# Ethernet-HPS.net
KiCad netlist of a schematic drawn in Altium Designer
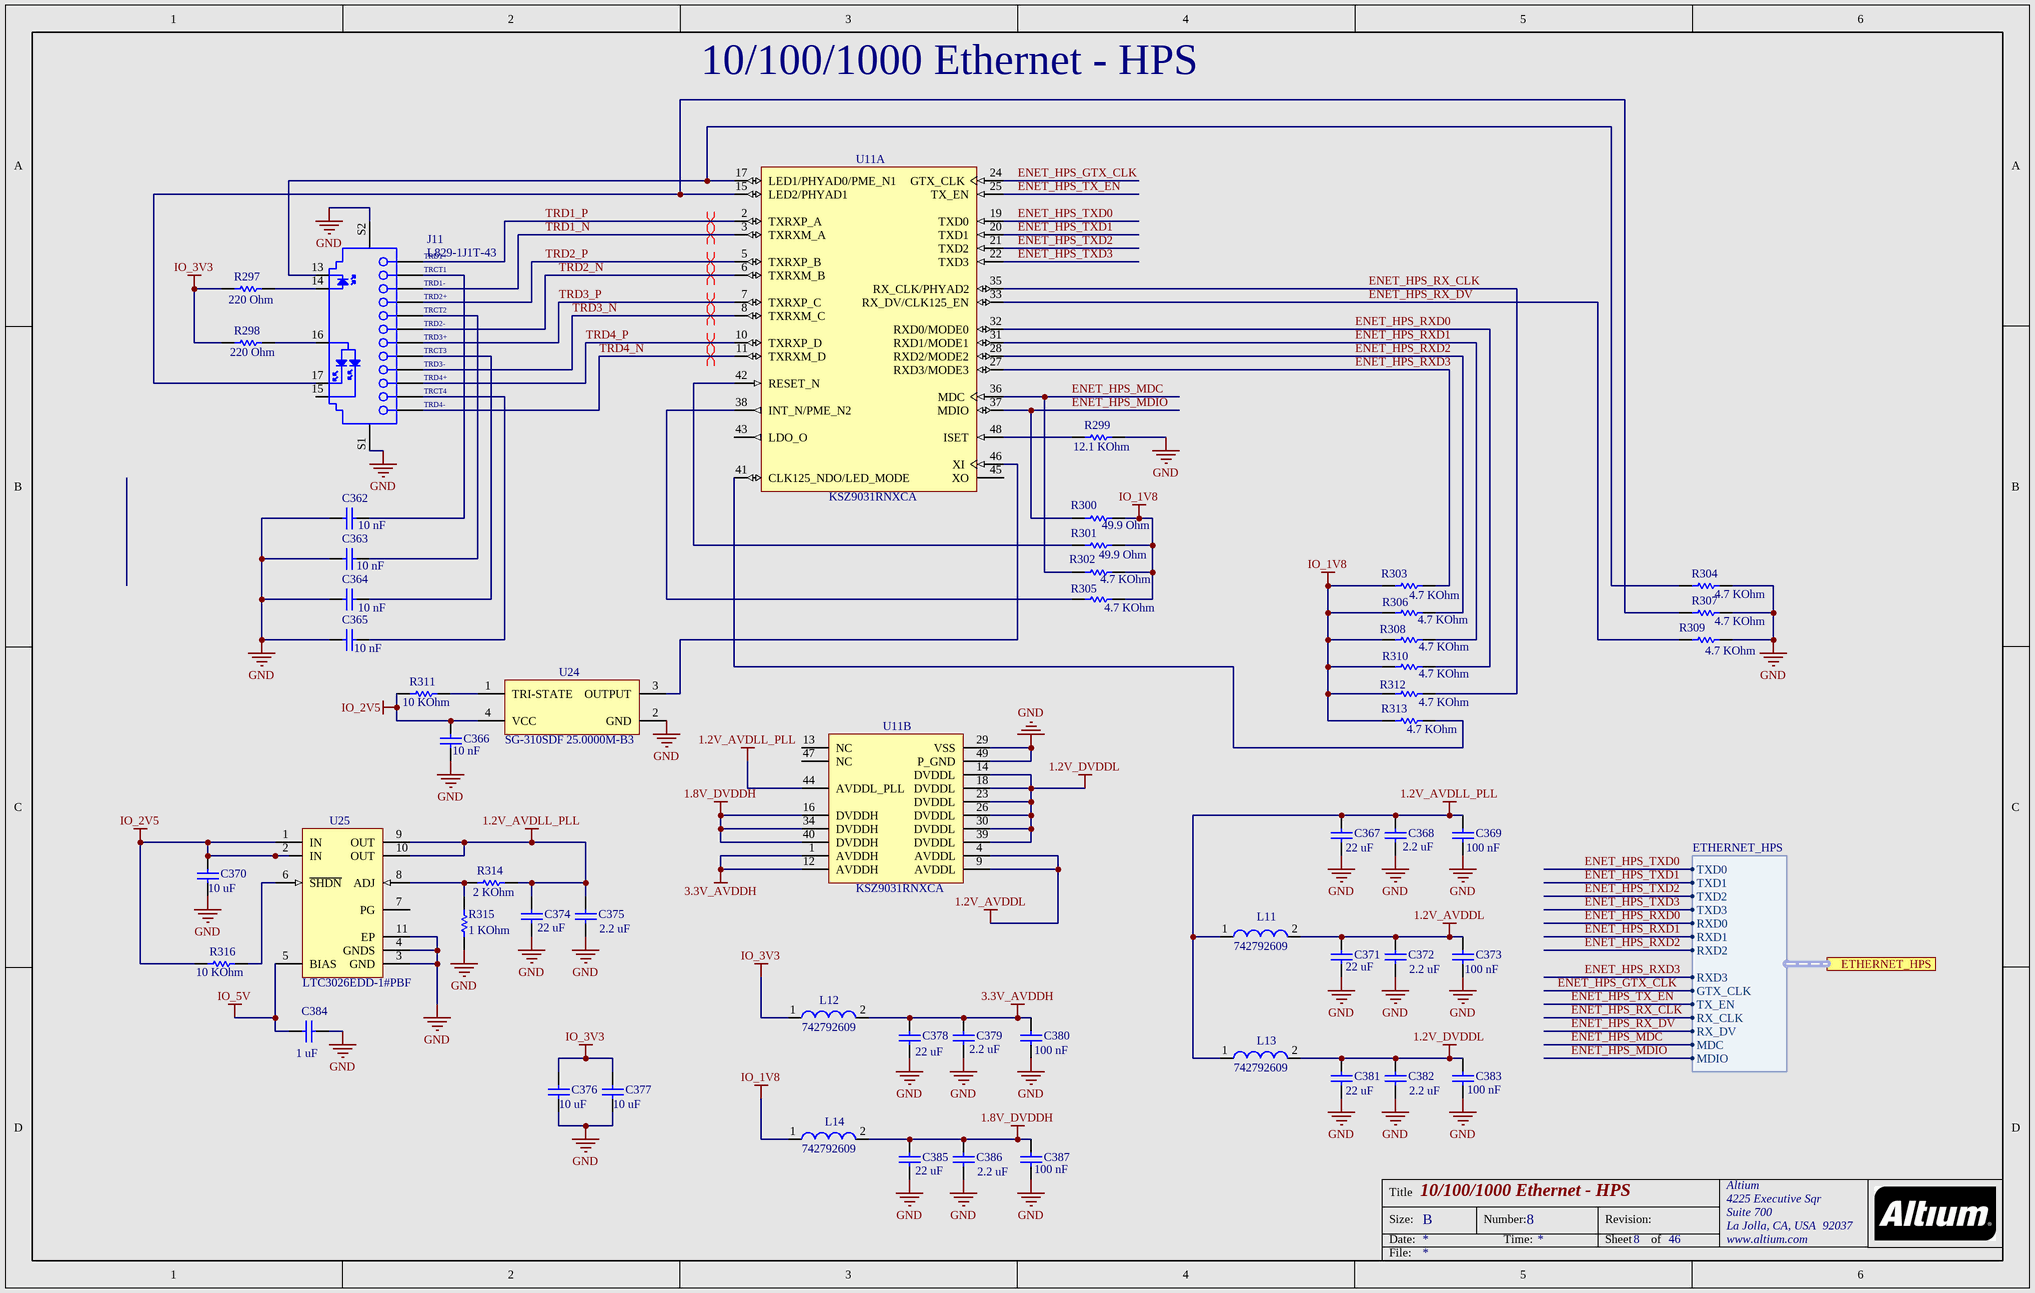
[diagram p0: Ethernet-HPS.SchDoc]

(export (version "E")
  (design (tool "Eeschema 10.0.6"))
  (components
    (comp (ref "C362")
      (value "GRM155R71H103KA88D")
      (footprint "CAPC1005X55X25ML05T10")
      (description "Chip Capacitor, 10 nF, +/- 10%, 50 V, -55 to 125 degC, 0402 (1005 Metric), RoHS, Tape and Reel")
      (fields
        (field (name "TOLERANCE") "10%")
        (field (name "CAPACITANCE") "10 nF")
        (field (name "MANUFACTURER") "Basic Passives")
      )
      (libsource (lib "Altium Content Vault") (part "CAP-NP-2"))
    )
    (comp (ref "C363")
      (value "GRM155R71H103KA88D")
      (footprint "CAPC1005X55X25ML05T10")
      (description "Chip Capacitor, 10 nF, +/- 10%, 50 V, -55 to 125 degC, 0402 (1005 Metric), RoHS, Tape and Reel")
      (fields
        (field (name "TOLERANCE") "10%")
        (field (name "CAPACITANCE") "10 nF")
        (field (name "MANUFACTURER") "Basic Passives")
      )
      (libsource (lib "Altium Content Vault") (part "CAP-NP-2"))
    )
    (comp (ref "C364")
      (value "GRM155R71H103KA88D")
      (footprint "CAPC1005X55X25ML05T10")
      (description "Chip Capacitor, 10 nF, +/- 10%, 50 V, -55 to 125 degC, 0402 (1005 Metric), RoHS, Tape and Reel")
      (fields
        (field (name "TOLERANCE") "10%")
        (field (name "CAPACITANCE") "10 nF")
        (field (name "MANUFACTURER") "Basic Passives")
      )
      (libsource (lib "Altium Content Vault") (part "CAP-NP-2"))
    )
    (comp (ref "C365")
      (value "GRM155R71H103KA88D")
      (footprint "CAPC1005X55X25ML05T10")
      (description "Chip Capacitor, 10 nF, +/- 10%, 50 V, -55 to 125 degC, 0402 (1005 Metric), RoHS, Tape and Reel")
      (fields
        (field (name "TOLERANCE") "10%")
        (field (name "CAPACITANCE") "10 nF")
        (field (name "MANUFACTURER") "Basic Passives")
      )
      (libsource (lib "Altium Content Vault") (part "CAP-NP-2"))
    )
    (comp (ref "C366")
      (value "GRM155R71H103KA88D")
      (footprint "CAPC1005X55X25ML05T10")
      (description "Chip Capacitor, 10 nF, +/- 10%, 50 V, -55 to 125 degC, 0402 (1005 Metric), RoHS, Tape and Reel")
      (fields
        (field (name "TOLERANCE") "10%")
        (field (name "CAPACITANCE") "10 nF")
        (field (name "MANUFACTURER") "Basic Passives")
      )
      (libsource (lib "Altium Content Vault") (part "CAP-NP-2"))
    )
    (comp (ref "C367")
      (value "GRM31CR61E226KE15L")
      (footprint "CAPC3216X180X55ML20T25")
      (description "Chip Capacitor, 22 uF, +/- 10%, 25 V, -55 to 85 degC, 1206 (3216 Metric), RoHS, Tape and Reel")
      (fields (field (name "TOLERANCE") "10%") (field (name "CAPACITANCE") "22 uF"))
      (libsource (lib "Altium Content Vault") (part "CAP-NP-2"))
    )
    (comp (ref "C368")
      (value "GRM188R61A225KE34x")
      (footprint "CAPC1608X90X35ML10T15")
      (description "Chip Capacitor, 2.2 uF, +/- 10%, 10 V, -55 to 85 degC, 0603 (1608 Metric), RoHS, Tape and Reel")
      (fields (field (name "TOLERANCE") "10%") (field (name "CAPACITANCE") "2.2 uF"))
      (libsource (lib "") (part "CAP-NP-2_1"))
    )
    (comp (ref "C369")
      (value "C1005X7R1E104M")
      (footprint "CAPC1005X55X10LL05")
      (description "Chip Capacitor, 0.1 uF, +/- 20%, 25 V, -55 to 125 degC, 0402 (1005 Metric), RoHS, Tape and Reel")
      (fields (field (name "TOLERANCE") "20%") (field (name "CAPACITANCE") "100 nF"))
      (libsource (lib "Altium Content Vault") (part "CAP-NP-2"))
    )
    (comp (ref "C370")
      (value "C2012X5R1C106K085AC")
      (footprint "CAPC2013X100X20NL20")
      (description "Chip Capacitor, 10 uF, +/- 10%, 16 V, -55 to 85 degC, 0805 (2012 Metric), RoHS, Tape and Reel")
      (fields (field (name "TOLERANCE") "10%") (field (name "CAPACITANCE") "10 uF"))
      (libsource (lib "") (part "CAP-NP-2_1"))
    )
    (comp (ref "C371")
      (value "GRM31CR61E226KE15L")
      (footprint "CAPC3216X180X55ML20T25")
      (description "Chip Capacitor, 22 uF, +/- 10%, 25 V, -55 to 85 degC, 1206 (3216 Metric), RoHS, Tape and Reel")
      (fields (field (name "TOLERANCE") "10%") (field (name "CAPACITANCE") "22 uF"))
      (libsource (lib "Altium Content Vault") (part "CAP-NP-2"))
    )
    (comp (ref "C372")
      (value "GRM188R61A225KE34x")
      (footprint "CAPC1608X90X35ML10T15")
      (description "Chip Capacitor, 2.2 uF, +/- 10%, 10 V, -55 to 85 degC, 0603 (1608 Metric), RoHS, Tape and Reel")
      (fields (field (name "TOLERANCE") "10%") (field (name "CAPACITANCE") "2.2 uF"))
      (libsource (lib "") (part "CAP-NP-2_1"))
    )
    (comp (ref "C373")
      (value "C1005X7R1E104M")
      (footprint "CAPC1005X55X10LL05")
      (description "Chip Capacitor, 0.1 uF, +/- 20%, 25 V, -55 to 125 degC, 0402 (1005 Metric), RoHS, Tape and Reel")
      (fields (field (name "TOLERANCE") "20%") (field (name "CAPACITANCE") "100 nF"))
      (libsource (lib "Altium Content Vault") (part "CAP-NP-2"))
    )
    (comp (ref "C374")
      (value "GRM31CR61E226KE15L")
      (footprint "CAPC3216X180X55ML20T25")
      (description "Chip Capacitor, 22 uF, +/- 10%, 25 V, -55 to 85 degC, 1206 (3216 Metric), RoHS, Tape and Reel")
      (fields (field (name "TOLERANCE") "10%") (field (name "CAPACITANCE") "22 uF"))
      (libsource (lib "Altium Content Vault") (part "CAP-NP-2"))
    )
    (comp (ref "C375")
      (value "GRM188R61A225KE34x")
      (footprint "CAPC1608X90X35ML10T15")
      (description "Chip Capacitor, 2.2 uF, +/- 10%, 10 V, -55 to 85 degC, 0603 (1608 Metric), RoHS, Tape and Reel")
      (fields (field (name "TOLERANCE") "10%") (field (name "CAPACITANCE") "2.2 uF"))
      (libsource (lib "") (part "CAP-NP-2_1"))
    )
    (comp (ref "C376")
      (value "C2012X5R1C106K085AC")
      (footprint "CAPC2013X100X20NL20")
      (description "Chip Capacitor, 10 uF, +/- 10%, 16 V, -55 to 85 degC, 0805 (2012 Metric), RoHS, Tape and Reel")
      (fields (field (name "TOLERANCE") "10%") (field (name "CAPACITANCE") "10 uF"))
      (libsource (lib "") (part "CAP-NP-2_1"))
    )
    (comp (ref "C377")
      (value "C2012X5R1C106K085AC")
      (footprint "CAPC2013X100X20NL20")
      (description "Chip Capacitor, 10 uF, +/- 10%, 16 V, -55 to 85 degC, 0805 (2012 Metric), RoHS, Tape and Reel")
      (fields (field (name "TOLERANCE") "10%") (field (name "CAPACITANCE") "10 uF"))
      (libsource (lib "") (part "CAP-NP-2_1"))
    )
    (comp (ref "C378")
      (value "GRM31CR61E226KE15L")
      (footprint "CAPC3216X180X55ML20T25")
      (description "Chip Capacitor, 22 uF, +/- 10%, 25 V, -55 to 85 degC, 1206 (3216 Metric), RoHS, Tape and Reel")
      (fields (field (name "TOLERANCE") "10%") (field (name "CAPACITANCE") "22 uF"))
      (libsource (lib "Altium Content Vault") (part "CAP-NP-2"))
    )
    (comp (ref "C379")
      (value "GRM188R61A225KE34x")
      (footprint "CAPC1608X90X35ML10T15")
      (description "Chip Capacitor, 2.2 uF, +/- 10%, 10 V, -55 to 85 degC, 0603 (1608 Metric), RoHS, Tape and Reel")
      (fields (field (name "TOLERANCE") "10%") (field (name "CAPACITANCE") "2.2 uF"))
      (libsource (lib "") (part "CAP-NP-2_1"))
    )
    (comp (ref "C380")
      (value "C1005X7R1E104M")
      (footprint "CAPC1005X55X10LL05")
      (description "Chip Capacitor, 0.1 uF, +/- 20%, 25 V, -55 to 125 degC, 0402 (1005 Metric), RoHS, Tape and Reel")
      (fields (field (name "TOLERANCE") "20%") (field (name "CAPACITANCE") "100 nF"))
      (libsource (lib "Altium Content Vault") (part "CAP-NP-2"))
    )
    (comp (ref "C381")
      (value "GRM31CR61E226KE15L")
      (footprint "CAPC3216X180X55ML20T25")
      (description "Chip Capacitor, 22 uF, +/- 10%, 25 V, -55 to 85 degC, 1206 (3216 Metric), RoHS, Tape and Reel")
      (fields (field (name "TOLERANCE") "10%") (field (name "CAPACITANCE") "22 uF"))
      (libsource (lib "Altium Content Vault") (part "CAP-NP-2"))
    )
    (comp (ref "C382")
      (value "GRM188R61A225KE34x")
      (footprint "CAPC1608X90X35ML10T15")
      (description "Chip Capacitor, 2.2 uF, +/- 10%, 10 V, -55 to 85 degC, 0603 (1608 Metric), RoHS, Tape and Reel")
      (fields (field (name "TOLERANCE") "10%") (field (name "CAPACITANCE") "2.2 uF"))
      (libsource (lib "") (part "CAP-NP-2_1"))
    )
    (comp (ref "C383")
      (value "C1005X7R1E104M")
      (footprint "CAPC1005X55X10LL05")
      (description "Chip Capacitor, 0.1 uF, +/- 20%, 25 V, -55 to 125 degC, 0402 (1005 Metric), RoHS, Tape and Reel")
      (fields (field (name "TOLERANCE") "20%") (field (name "CAPACITANCE") "100 nF"))
      (libsource (lib "Altium Content Vault") (part "CAP-NP-2"))
    )
    (comp (ref "C384")
      (value "CGB2A1X5R1E105K033BC")
      (footprint "CAPC1005X33X10LL5")
      (description "Chip Capacitor, 1 uF, +/- 10%, 25 V, -55 to 85 degC, 0402 (1005 Metric), RoHS, Tape and Reel")
      (fields (field (name "CAPACITANCE") "1 uF") (field (name "TOLERANCE") "10%"))
      (libsource (lib "") (part "CAP-NP-2_1"))
    )
    (comp (ref "C385")
      (value "GRM31CR61E226KE15L")
      (footprint "CAPC3216X180X55ML20T25")
      (description "Chip Capacitor, 22 uF, +/- 10%, 25 V, -55 to 85 degC, 1206 (3216 Metric), RoHS, Tape and Reel")
      (fields (field (name "TOLERANCE") "10%") (field (name "CAPACITANCE") "22 uF"))
      (libsource (lib "Altium Content Vault") (part "CAP-NP-2"))
    )
    (comp (ref "C386")
      (value "GRM188R61A225KE34x")
      (footprint "CAPC1608X90X35ML10T15")
      (description "Chip Capacitor, 2.2 uF, +/- 10%, 10 V, -55 to 85 degC, 0603 (1608 Metric), RoHS, Tape and Reel")
      (fields (field (name "TOLERANCE") "10%") (field (name "CAPACITANCE") "2.2 uF"))
      (libsource (lib "") (part "CAP-NP-2_1"))
    )
    (comp (ref "C387")
      (value "C1005X7R1E104M")
      (footprint "CAPC1005X55X10LL05")
      (description "Chip Capacitor, 0.1 uF, +/- 20%, 25 V, -55 to 125 degC, 0402 (1005 Metric), RoHS, Tape and Reel")
      (fields (field (name "TOLERANCE") "20%") (field (name "CAPACITANCE") "100 nF"))
      (libsource (lib "Altium Content Vault") (part "CAP-NP-2"))
    )
    (comp (ref "J11")
      (value "L829-1J1T-43")
      (footprint "BELS-L829-1J1T-43_V")
      (description "Gigabit MagJack(R) Ultra Low Profile, 10/100/1000 Base-T, 19-Pin THD, RoHS, Tray")
      (libsource (lib "Altium Content Vault") (part "RJ45-17-2SHLD"))
    )
    (comp (ref "L11")
      (value "742792609")
      (footprint "SMD-0603")
      (description "SMD EMI Suppression Ferrite Bead WE-CBF, Z = 30 Ohm")
      (libsource (lib "Altium Content Vault") (part "CMP-0220-00193-1"))
    )
    (comp (ref "L12")
      (value "742792609")
      (footprint "SMD-0603")
      (description "SMD EMI Suppression Ferrite Bead WE-CBF, Z = 30 Ohm")
      (libsource (lib "Altium Content Vault") (part "CMP-0220-00193-1"))
    )
    (comp (ref "L13")
      (value "742792609")
      (footprint "SMD-0603")
      (description "SMD EMI Suppression Ferrite Bead WE-CBF, Z = 30 Ohm")
      (libsource (lib "Altium Content Vault") (part "CMP-0220-00193-1"))
    )
    (comp (ref "L14")
      (value "742792609")
      (footprint "SMD-0603")
      (description "SMD EMI Suppression Ferrite Bead WE-CBF, Z = 30 Ohm")
      (libsource (lib "Altium Content Vault") (part "CMP-0220-00193-1"))
    )
    (comp (ref "R297")
      (value "ERJ-2GEJ221X")
      (footprint "RESC1005X40X25LL05T05")
      (description "Chip Resistor, 220 Ohm, +/- 5%, 100 mW, -55 to 155 degC, 0402 (1005 Metric), RoHS, Tape and Reel")
      (fields
        (field (name "RESISTANCE") "220 Ohm")
        (field (name "TOLERANCE") "5%")
        (field (name "MANUFACTURER") "Basic Passives")
      )
      (libsource (lib "Altium Content Vault") (part "RES-2"))
    )
    (comp (ref "R298")
      (value "ERJ-2GEJ221X")
      (footprint "RESC1005X40X25LL05T05")
      (description "Chip Resistor, 220 Ohm, +/- 5%, 100 mW, -55 to 155 degC, 0402 (1005 Metric), RoHS, Tape and Reel")
      (fields
        (field (name "RESISTANCE") "220 Ohm")
        (field (name "TOLERANCE") "5%")
        (field (name "MANUFACTURER") "Basic Passives")
      )
      (libsource (lib "Altium Content Vault") (part "RES-2"))
    )
    (comp (ref "R299")
      (value "CRCW040212K1FKED")
      (footprint "RESC1005X40X25LL05T05")
      (description "Chip Resistor, 12.1 KOhm, +/- 1%, 63 mW, -55 to 155 degC, 0402 (1005 Metric), RoHS, Tape and Reel")
      (fields
        (field (name "RESISTANCE") "12.1 KOhm")
        (field (name "TOLERANCE") "1%")
        (field (name "MANUFACTURER") "Basic Passives")
      )
      (libsource (lib "Altium Content Vault") (part "RES-2"))
    )
    (comp (ref "R300")
      (value "NRC04F49R9TRF")
      (footprint "RESC1005X35X25NL8T10")
      (description "Chip Resistor, 49.9 Ohm, +/- 1%, 0.06 W, -55 to 155 degC, 0402 (1005 Metric), RoHS, Tape and Reel")
      (fields (field (name "TOLERANCE") "1%") (field (name "RESISTANCE") "49.9 Ohm"))
      (libsource (lib "Altium Content Vault") (part "RES-2"))
    )
    (comp (ref "R301")
      (value "NRC04F49R9TRF")
      (footprint "RESC1005X35X25NL8T10")
      (description "Chip Resistor, 49.9 Ohm, +/- 1%, 0.06 W, -55 to 155 degC, 0402 (1005 Metric), RoHS, Tape and Reel")
      (fields (field (name "TOLERANCE") "1%") (field (name "RESISTANCE") "49.9 Ohm"))
      (libsource (lib "Altium Content Vault") (part "RES-2"))
    )
    (comp (ref "R302")
      (value "ERJ-2RKF4701X")
      (footprint "RESC1005X40X25LL05T05")
      (description "Chip Resistor, 4.7 KOhm, +/- 1%, 0.1 W, -55 to 155 degC, 0402 (1005 Metric), RoHS, Tape and Reel")
      (fields (field (name "TOLERANCE") "1%") (field (name "RESISTANCE") "4.7 KOhm"))
      (libsource (lib "Altium Content Vault") (part "RES-2"))
    )
    (comp (ref "R303")
      (value "ERJ-2RKF4701X")
      (footprint "RESC1005X40X25LL05T05")
      (description "Chip Resistor, 4.7 KOhm, +/- 1%, 0.1 W, -55 to 155 degC, 0402 (1005 Metric), RoHS, Tape and Reel")
      (fields (field (name "TOLERANCE") "1%") (field (name "RESISTANCE") "4.7 KOhm"))
      (libsource (lib "Altium Content Vault") (part "RES-2"))
    )
    (comp (ref "R304")
      (value "ERJ-2RKF4701X")
      (footprint "RESC1005X40X25LL05T05")
      (description "Chip Resistor, 4.7 KOhm, +/- 1%, 0.1 W, -55 to 155 degC, 0402 (1005 Metric), RoHS, Tape and Reel")
      (fields (field (name "TOLERANCE") "1%") (field (name "RESISTANCE") "4.7 KOhm"))
      (libsource (lib "Altium Content Vault") (part "RES-2"))
    )
    (comp (ref "R305")
      (value "ERJ-2RKF4701X")
      (footprint "RESC1005X40X25LL05T05")
      (description "Chip Resistor, 4.7 KOhm, +/- 1%, 0.1 W, -55 to 155 degC, 0402 (1005 Metric), RoHS, Tape and Reel")
      (fields (field (name "TOLERANCE") "1%") (field (name "RESISTANCE") "4.7 KOhm"))
      (libsource (lib "Altium Content Vault") (part "RES-2"))
    )
    (comp (ref "R306")
      (value "ERJ-2RKF4701X")
      (footprint "RESC1005X40X25LL05T05")
      (description "Chip Resistor, 4.7 KOhm, +/- 1%, 0.1 W, -55 to 155 degC, 0402 (1005 Metric), RoHS, Tape and Reel")
      (fields (field (name "TOLERANCE") "1%") (field (name "RESISTANCE") "4.7 KOhm"))
      (libsource (lib "Altium Content Vault") (part "RES-2"))
    )
    (comp (ref "R307")
      (value "ERJ-2RKF4701X")
      (footprint "RESC1005X40X25LL05T05")
      (description "Chip Resistor, 4.7 KOhm, +/- 1%, 0.1 W, -55 to 155 degC, 0402 (1005 Metric), RoHS, Tape and Reel")
      (fields (field (name "TOLERANCE") "1%") (field (name "RESISTANCE") "4.7 KOhm"))
      (libsource (lib "Altium Content Vault") (part "RES-2"))
    )
    (comp (ref "R308")
      (value "ERJ-2RKF4701X")
      (footprint "RESC1005X40X25LL05T05")
      (description "Chip Resistor, 4.7 KOhm, +/- 1%, 0.1 W, -55 to 155 degC, 0402 (1005 Metric), RoHS, Tape and Reel")
      (fields (field (name "TOLERANCE") "1%") (field (name "RESISTANCE") "4.7 KOhm"))
      (libsource (lib "Altium Content Vault") (part "RES-2"))
    )
    (comp (ref "R309")
      (value "ERJ-2RKF4701X")
      (footprint "RESC1005X40X25LL05T05")
      (description "Chip Resistor, 4.7 KOhm, +/- 1%, 0.1 W, -55 to 155 degC, 0402 (1005 Metric), RoHS, Tape and Reel")
      (fields (field (name "TOLERANCE") "1%") (field (name "RESISTANCE") "4.7 KOhm"))
      (libsource (lib "Altium Content Vault") (part "RES-2"))
    )
    (comp (ref "R310")
      (value "ERJ-2RKF4701X")
      (footprint "RESC1005X40X25LL05T05")
      (description "Chip Resistor, 4.7 KOhm, +/- 1%, 0.1 W, -55 to 155 degC, 0402 (1005 Metric), RoHS, Tape and Reel")
      (fields (field (name "TOLERANCE") "1%") (field (name "RESISTANCE") "4.7 KOhm"))
      (libsource (lib "Altium Content Vault") (part "RES-2"))
    )
    (comp (ref "R311")
      (value "ERJ-2RKF1002X")
      (footprint "RESC1005X40X25NL05T05")
      (description "Chip Resistor, 10 KOhm, +/- 1%, 100 mW, -55 to 155 degC, 0402 (1005 Metric), RoHS, Tape and Reel")
      (fields
        (field (name "TOLERANCE") "1%")
        (field (name "RESISTANCE") "10 KOhm")
        (field (name "MANUFACTURER") "Basic Passives")
      )
      (libsource (lib "Altium Content Vault") (part "RES-2"))
    )
    (comp (ref "R312")
      (value "ERJ-2RKF4701X")
      (footprint "RESC1005X40X25LL05T05")
      (description "Chip Resistor, 4.7 KOhm, +/- 1%, 0.1 W, -55 to 155 degC, 0402 (1005 Metric), RoHS, Tape and Reel")
      (fields (field (name "TOLERANCE") "1%") (field (name "RESISTANCE") "4.7 KOhm"))
      (libsource (lib "Altium Content Vault") (part "RES-2"))
    )
    (comp (ref "R313")
      (value "ERJ-2RKF4701X")
      (footprint "RESC1005X40X25LL05T05")
      (description "Chip Resistor, 4.7 KOhm, +/- 1%, 0.1 W, -55 to 155 degC, 0402 (1005 Metric), RoHS, Tape and Reel")
      (fields (field (name "TOLERANCE") "1%") (field (name "RESISTANCE") "4.7 KOhm"))
      (libsource (lib "Altium Content Vault") (part "RES-2"))
    )
    (comp (ref "R314")
      (value "ERJ-2RKF2001X")
      (footprint "RESC1005X40X25NL05T05")
      (description "Chip Resistor, 2 KOhm, +/- 1%, 100 mW, -55 to 155 degC, 0402 (1005 Metric), RoHS, Tape and Reel")
      (fields
        (field (name "TOLERANCE") "1%")
        (field (name "RESISTANCE") "2 KOhm")
        (field (name "MANUFACTURER") "Basic Passives")
      )
      (libsource (lib "Altium Content Vault") (part "RES-2"))
    )
    (comp (ref "R315")
      (value "ERJ-2RKF1001X")
      (footprint "RESC1005X40X25LL05T05")
      (description "Chip Resistor, 1 KOhm, +/- 1%, 100 mW, -55 to 155 degC, 0402 (1005 Metric), RoHS, Tape and Reel")
      (fields
        (field (name "RESISTANCE") "1 KOhm")
        (field (name "TOLERANCE") "1%")
        (field (name "MANUFACTURER") "Basic Passives")
      )
      (libsource (lib "Altium Content Vault") (part "RES-2"))
    )
    (comp (ref "R316")
      (value "ERJ-2RKF1002X")
      (footprint "RESC1005X40X25NL05T05")
      (description "Chip Resistor, 10 KOhm, +/- 1%, 100 mW, -55 to 155 degC, 0402 (1005 Metric), RoHS, Tape and Reel")
      (fields
        (field (name "TOLERANCE") "1%")
        (field (name "RESISTANCE") "10 KOhm")
        (field (name "MANUFACTURER") "Basic Passives")
      )
      (libsource (lib "Altium Content Vault") (part "RES-2"))
    )
    (comp (ref "U11")
      (value "KSZ9031RNXCA")
      (footprint "MICL-QFN-48_V")
      (description "Gigabit Ethernet Transceiver with RGMII Support, 1.14 to 1.26 V, 0 to 70 degC, 48-Pin QFN, RoHS")
      (fields (field (name "MANUFACTURER") "Micrel"))
      (libsource (lib "Altium Content Vault") (part "MICL-KSZ9031RNX-48"))
    )
    (comp (ref "U24")
      (value "SG-310SDF 25.0000M-B3")
      (footprint "EPSON-SG-310-4_V")
      (description "Crystal Oscillator (SPXO), 2.5 V, 25 MHz, -20 to 70 degC, 4-Pin SMD, RoHS, Tape and Reel")
      (libsource (lib "Altium Content Vault") (part "XTAL-1-3-4_B"))
    )
    (comp (ref "U25")
      (value "LTC3026EDD-1#PBF")
      (footprint "LT-DD-10_V")
      (fields (field (name "MANUFACTURER") "Linear Technology"))
      (libsource (lib "Altium Content Vault") (part "LT-LTC3026-1-10"))
    )
  )
  (nets
    (net (code "2") (name "/ENET_HPS_GTX_CLK") (class "Default")
      (node (ref "U11") (pin "24") (pinfunction "GTX_CLK_24") (pintype "input"))
    )
    (net (code "3") (name "/ENET_HPS_MDC") (class "Default")
      (node (ref "R302") (pin "1") (pinfunction "1_1") (pintype "passive"))
      (node (ref "U11") (pin "36") (pinfunction "MDC_36") (pintype "input"))
    )
    (net (code "4") (name "/ENET_HPS_MDIO") (class "Default")
      (node (ref "R300") (pin "1") (pinfunction "1_1") (pintype "passive"))
      (node (ref "U11") (pin "37") (pinfunction "MDIO_37") (pintype "bidirectional"))
    )
    (net (code "5") (name "/ENET_HPS_RXD0") (class "Default")
      (node (ref "R310") (pin "2") (pinfunction "2_2") (pintype "passive"))
      (node (ref "U11") (pin "32") (pinfunction "RXD0/MODE0_32") (pintype "bidirectional"))
    )
    (net (code "6") (name "/ENET_HPS_RXD1") (class "Default")
      (node (ref "R308") (pin "2") (pinfunction "2_2") (pintype "passive"))
      (node (ref "U11") (pin "31") (pinfunction "RXD1/MODE1_31") (pintype "bidirectional"))
    )
    (net (code "7") (name "/ENET_HPS_RXD2") (class "Default")
      (node (ref "R306") (pin "2") (pinfunction "2_2") (pintype "passive"))
      (node (ref "U11") (pin "28") (pinfunction "RXD2/MODE2_28") (pintype "bidirectional"))
    )
    (net (code "8") (name "/ENET_HPS_RXD3") (class "Default")
      (node (ref "R303") (pin "2") (pinfunction "2_2") (pintype "passive"))
      (node (ref "U11") (pin "27") (pinfunction "RXD3/MODE3_27") (pintype "bidirectional"))
    )
    (net (code "9") (name "/ENET_HPS_RX_CLK") (class "Default")
      (node (ref "R312") (pin "2") (pinfunction "2_2") (pintype "passive"))
      (node (ref "U11") (pin "35") (pinfunction "RX_CLK/PHYAD2_35") (pintype "bidirectional"))
    )
    (net (code "10") (name "/ENET_HPS_RX_DV") (class "Default")
      (node (ref "R309") (pin "1") (pinfunction "1_1") (pintype "passive"))
      (node (ref "U11") (pin "33") (pinfunction "RX_DV/CLK125_EN_33") (pintype "bidirectional"))
    )
    (net (code "11") (name "/ENET_HPS_TXD0") (class "Default")
      (node (ref "U11") (pin "19") (pinfunction "TXD0_19") (pintype "input"))
    )
    (net (code "12") (name "/ENET_HPS_TXD1") (class "Default")
      (node (ref "U11") (pin "20") (pinfunction "TXD1_20") (pintype "input"))
    )
    (net (code "13") (name "/ENET_HPS_TXD2") (class "Default")
      (node (ref "U11") (pin "21") (pinfunction "TXD2_21") (pintype "input"))
    )
    (net (code "14") (name "/ENET_HPS_TXD3") (class "Default")
      (node (ref "U11") (pin "22") (pinfunction "TXD3_22") (pintype "input"))
    )
    (net (code "15") (name "/ENET_HPS_TX_EN") (class "Default")
      (node (ref "U11") (pin "25") (pinfunction "TX_EN_25") (pintype "input"))
    )
    (net (code "16") (name "/TRD1_N") (class "Default")
      (node (ref "J11") (pin "3") (pinfunction "TRD1-_3") (pintype "passive"))
      (node (ref "U11") (pin "3") (pinfunction "TXRXM_A_3") (pintype "bidirectional"))
    )
    (net (code "17") (name "/TRD1_P") (class "Default")
      (node (ref "J11") (pin "1") (pinfunction "TRD1+_1") (pintype "passive"))
      (node (ref "U11") (pin "2") (pinfunction "TXRXP_A_2") (pintype "bidirectional"))
    )
    (net (code "18") (name "/TRD2_N") (class "Default")
      (node (ref "J11") (pin "6") (pinfunction "TRD2-_6") (pintype "passive"))
      (node (ref "U11") (pin "6") (pinfunction "TXRXM_B_6") (pintype "bidirectional"))
    )
    (net (code "19") (name "/TRD2_P") (class "Default")
      (node (ref "J11") (pin "4") (pinfunction "TRD2+_4") (pintype "passive"))
      (node (ref "U11") (pin "5") (pinfunction "TXRXP_B_5") (pintype "bidirectional"))
    )
    (net (code "20") (name "/TRD3_N") (class "Default")
      (node (ref "J11") (pin "9") (pinfunction "TRD3-_9") (pintype "passive"))
      (node (ref "U11") (pin "8") (pinfunction "TXRXM_C_8") (pintype "bidirectional"))
    )
    (net (code "21") (name "/TRD3_P") (class "Default")
      (node (ref "J11") (pin "7") (pinfunction "TRD3+_7") (pintype "passive"))
      (node (ref "U11") (pin "7") (pinfunction "TXRXP_C_7") (pintype "bidirectional"))
    )
    (net (code "22") (name "/TRD4_N") (class "Default")
      (node (ref "J11") (pin "12") (pinfunction "TRD4-_12") (pintype "passive"))
      (node (ref "U11") (pin "11") (pinfunction "TXRXM_D_11") (pintype "bidirectional"))
    )
    (net (code "23") (name "/TRD4_P") (class "Default")
      (node (ref "J11") (pin "10") (pinfunction "TRD4+_10") (pintype "passive"))
      (node (ref "U11") (pin "10") (pinfunction "TXRXP_D_10") (pintype "bidirectional"))
    )
    (net (code "25") (name "1.2V_AVDDL") (class "Default")
      (node (ref "C371") (pin "2") (pinfunction "2_2") (pintype "passive"))
      (node (ref "C372") (pin "2") (pinfunction "2_2") (pintype "passive"))
      (node (ref "C373") (pin "2") (pinfunction "2_2") (pintype "passive"))
      (node (ref "L11") (pin "2") (pinfunction "2_2") (pintype "passive"))
      (node (ref "U11") (pin "4") (pinfunction "AVDDL_4") (pintype "power_in"))
      (node (ref "U11") (pin "9") (pinfunction "AVDDL_9") (pintype "power_in"))
    )
    (net (code "26") (name "1.2V_AVDLL_PLL") (class "Default")
      (node (ref "C367") (pin "2") (pinfunction "2_2") (pintype "passive"))
      (node (ref "C368") (pin "2") (pinfunction "2_2") (pintype "passive"))
      (node (ref "C369") (pin "2") (pinfunction "2_2") (pintype "passive"))
      (node (ref "C374") (pin "2") (pinfunction "2_2") (pintype "passive"))
      (node (ref "C375") (pin "2") (pinfunction "2_2") (pintype "passive"))
      (node (ref "L11") (pin "1") (pinfunction "1_1") (pintype "passive"))
      (node (ref "L13") (pin "1") (pinfunction "1_1") (pintype "passive"))
      (node (ref "R314") (pin "2") (pinfunction "2_2") (pintype "passive"))
      (node (ref "U11") (pin "44") (pinfunction "AVDDL_PLL_44") (pintype "power_in"))
      (node (ref "U25") (pin "10") (pinfunction "OUT_10") (pintype "power_in"))
      (node (ref "U25") (pin "9") (pinfunction "OUT_9") (pintype "power_in"))
    )
    (net (code "27") (name "1.2V_DVDDL") (class "Default")
      (node (ref "C381") (pin "2") (pinfunction "2_2") (pintype "passive"))
      (node (ref "C382") (pin "2") (pinfunction "2_2") (pintype "passive"))
      (node (ref "C383") (pin "2") (pinfunction "2_2") (pintype "passive"))
      (node (ref "L13") (pin "2") (pinfunction "2_2") (pintype "passive"))
      (node (ref "U11") (pin "14") (pinfunction "DVDDL_14") (pintype "power_in"))
      (node (ref "U11") (pin "18") (pinfunction "DVDDL_18") (pintype "power_in"))
      (node (ref "U11") (pin "23") (pinfunction "DVDDL_23") (pintype "power_in"))
      (node (ref "U11") (pin "26") (pinfunction "DVDDL_26") (pintype "power_in"))
      (node (ref "U11") (pin "30") (pinfunction "DVDDL_30") (pintype "power_in"))
      (node (ref "U11") (pin "39") (pinfunction "DVDDL_39") (pintype "power_in"))
    )
    (net (code "28") (name "1.8V_DVDDH") (class "Default")
      (node (ref "C385") (pin "2") (pinfunction "2_2") (pintype "passive"))
      (node (ref "C386") (pin "2") (pinfunction "2_2") (pintype "passive"))
      (node (ref "C387") (pin "1") (pinfunction "1_1") (pintype "passive"))
      (node (ref "L14") (pin "2") (pinfunction "2_2") (pintype "passive"))
      (node (ref "U11") (pin "16") (pinfunction "DVDDH_16") (pintype "power_in"))
      (node (ref "U11") (pin "34") (pinfunction "DVDDH_34") (pintype "power_in"))
      (node (ref "U11") (pin "40") (pinfunction "DVDDH_40") (pintype "power_in"))
    )
    (net (code "29") (name "3.3V_AVDDH") (class "Default")
      (node (ref "C378") (pin "2") (pinfunction "2_2") (pintype "passive"))
      (node (ref "C379") (pin "2") (pinfunction "2_2") (pintype "passive"))
      (node (ref "C380") (pin "2") (pinfunction "2_2") (pintype "passive"))
      (node (ref "L12") (pin "2") (pinfunction "2_2") (pintype "passive"))
      (node (ref "U11") (pin "1") (pinfunction "AVDDH_1") (pintype "power_in"))
      (node (ref "U11") (pin "12") (pinfunction "AVDDH_12") (pintype "power_in"))
    )
    (net (code "30") (name "GND") (class "Default")
      (node (ref "C362") (pin "1") (pinfunction "1_1") (pintype "passive"))
      (node (ref "C363") (pin "1") (pinfunction "1_1") (pintype "passive"))
      (node (ref "C364") (pin "1") (pinfunction "1_1") (pintype "passive"))
      (node (ref "C365") (pin "1") (pinfunction "1_1") (pintype "passive"))
      (node (ref "C366") (pin "1") (pinfunction "1_1") (pintype "passive"))
      (node (ref "C367") (pin "1") (pinfunction "1_1") (pintype "passive"))
      (node (ref "C368") (pin "1") (pinfunction "1_1") (pintype "passive"))
      (node (ref "C369") (pin "1") (pinfunction "1_1") (pintype "passive"))
      (node (ref "C370") (pin "1") (pinfunction "1_1") (pintype "passive"))
      (node (ref "C371") (pin "1") (pinfunction "1_1") (pintype "passive"))
      (node (ref "C372") (pin "1") (pinfunction "1_1") (pintype "passive"))
      (node (ref "C373") (pin "1") (pinfunction "1_1") (pintype "passive"))
      (node (ref "C374") (pin "1") (pinfunction "1_1") (pintype "passive"))
      (node (ref "C375") (pin "1") (pinfunction "1_1") (pintype "passive"))
      (node (ref "C376") (pin "1") (pinfunction "1_1") (pintype "passive"))
      (node (ref "C377") (pin "1") (pinfunction "1_1") (pintype "passive"))
      (node (ref "C378") (pin "1") (pinfunction "1_1") (pintype "passive"))
      (node (ref "C379") (pin "1") (pinfunction "1_1") (pintype "passive"))
      (node (ref "C380") (pin "1") (pinfunction "1_1") (pintype "passive"))
      (node (ref "C381") (pin "1") (pinfunction "1_1") (pintype "passive"))
      (node (ref "C382") (pin "1") (pinfunction "1_1") (pintype "passive"))
      (node (ref "C383") (pin "1") (pinfunction "1_1") (pintype "passive"))
      (node (ref "C384") (pin "1") (pinfunction "1_1") (pintype "passive"))
      (node (ref "C385") (pin "1") (pinfunction "1_1") (pintype "passive"))
      (node (ref "C386") (pin "1") (pinfunction "1_1") (pintype "passive"))
      (node (ref "C387") (pin "2") (pinfunction "2_2") (pintype "passive"))
      (node (ref "J11") (pin "S1") (pinfunction "S1_S1") (pintype "passive"))
      (node (ref "J11") (pin "S2") (pinfunction "S2_S2") (pintype "passive"))
      (node (ref "R299") (pin "2") (pinfunction "2_2") (pintype "passive"))
      (node (ref "R304") (pin "2") (pinfunction "2_2") (pintype "passive"))
      (node (ref "R307") (pin "2") (pinfunction "2_2") (pintype "passive"))
      (node (ref "R309") (pin "2") (pinfunction "2_2") (pintype "passive"))
      (node (ref "R315") (pin "1") (pinfunction "1_1") (pintype "passive"))
      (node (ref "U11") (pin "29") (pinfunction "VSS_29") (pintype "power_in"))
      (node (ref "U11") (pin "49") (pinfunction "P_GND_49") (pintype "power_in"))
      (node (ref "U24") (pin "2") (pinfunction "GND_2") (pintype "power_in"))
      (node (ref "U25") (pin "11") (pinfunction "EP_11") (pintype "power_in"))
      (node (ref "U25") (pin "3") (pinfunction "GND_3") (pintype "power_in"))
      (node (ref "U25") (pin "4") (pinfunction "GNDS_4") (pintype "power_in"))
    )
    (net (code "31") (name "IO_1V8") (class "Default")
      (node (ref "L14") (pin "1") (pinfunction "1_1") (pintype "passive"))
      (node (ref "R300") (pin "2") (pinfunction "2_2") (pintype "passive"))
      (node (ref "R301") (pin "2") (pinfunction "2_2") (pintype "passive"))
      (node (ref "R302") (pin "2") (pinfunction "2_2") (pintype "passive"))
      (node (ref "R303") (pin "1") (pinfunction "1_1") (pintype "passive"))
      (node (ref "R305") (pin "2") (pinfunction "2_2") (pintype "passive"))
      (node (ref "R306") (pin "1") (pinfunction "1_1") (pintype "passive"))
      (node (ref "R308") (pin "1") (pinfunction "1_1") (pintype "passive"))
      (node (ref "R310") (pin "1") (pinfunction "1_1") (pintype "passive"))
      (node (ref "R312") (pin "1") (pinfunction "1_1") (pintype "passive"))
      (node (ref "R313") (pin "1") (pinfunction "1_1") (pintype "passive"))
    )
    (net (code "32") (name "IO_2V5") (class "Default")
      (node (ref "C366") (pin "2") (pinfunction "2_2") (pintype "passive"))
      (node (ref "C370") (pin "2") (pinfunction "2_2") (pintype "passive"))
      (node (ref "R311") (pin "1") (pinfunction "1_1") (pintype "passive"))
      (node (ref "R316") (pin "1") (pinfunction "1_1") (pintype "passive"))
      (node (ref "U24") (pin "4") (pinfunction "VCC_4") (pintype "power_in"))
      (node (ref "U25") (pin "1") (pinfunction "IN_1") (pintype "power_in"))
      (node (ref "U25") (pin "2") (pinfunction "IN_2") (pintype "power_in"))
    )
    (net (code "33") (name "IO_3V3") (class "Default")
      (node (ref "C376") (pin "2") (pinfunction "2_2") (pintype "passive"))
      (node (ref "C377") (pin "2") (pinfunction "2_2") (pintype "passive"))
      (node (ref "L12") (pin "1") (pinfunction "1_1") (pintype "passive"))
      (node (ref "R297") (pin "1") (pinfunction "1_1") (pintype "passive"))
      (node (ref "R298") (pin "1") (pinfunction "1_1") (pintype "passive"))
    )
    (net (code "34") (name "IO_5V") (class "Default")
      (node (ref "C384") (pin "2") (pinfunction "2_2") (pintype "passive"))
      (node (ref "U25") (pin "5") (pinfunction "BIAS_5") (pintype "power_in"))
    )
    (net (code "35") (name "Net-(J11-Pad14)") (class "Default")
      (node (ref "J11") (pin "14") (pinfunction "14_14") (pintype "passive"))
      (node (ref "R297") (pin "2") (pinfunction "2_2") (pintype "passive"))
    )
    (net (code "36") (name "Net-(J11-Pad16)") (class "Default")
      (node (ref "J11") (pin "16") (pinfunction "16_16") (pintype "passive"))
      (node (ref "R298") (pin "2") (pinfunction "2_2") (pintype "passive"))
    )
    (net (code "37") (name "Net-(J11-TRCT1)") (class "Default")
      (node (ref "C362") (pin "2") (pinfunction "2_2") (pintype "passive"))
      (node (ref "J11") (pin "2") (pinfunction "TRCT1_2") (pintype "passive"))
    )
    (net (code "38") (name "Net-(J11-TRCT2)") (class "Default")
      (node (ref "C363") (pin "2") (pinfunction "2_2") (pintype "passive"))
      (node (ref "J11") (pin "5") (pinfunction "TRCT2_5") (pintype "passive"))
    )
    (net (code "39") (name "Net-(J11-TRCT3)") (class "Default")
      (node (ref "C364") (pin "2") (pinfunction "2_2") (pintype "passive"))
      (node (ref "J11") (pin "8") (pinfunction "TRCT3_8") (pintype "passive"))
    )
    (net (code "40") (name "Net-(J11-TRCT4)") (class "Default")
      (node (ref "C365") (pin "2") (pinfunction "2_2") (pintype "passive"))
      (node (ref "J11") (pin "11") (pinfunction "TRCT4_11") (pintype "passive"))
    )
    (net (code "41") (name "Net-(U11A-CLK125_NDO{slash}LED_MODE)") (class "Default")
      (node (ref "R313") (pin "2") (pinfunction "2_2") (pintype "passive"))
      (node (ref "U11") (pin "41") (pinfunction "CLK125_NDO/LED_MODE_41") (pintype "bidirectional"))
    )
    (net (code "42") (name "Net-(U11A-INT_N{slash}PME_N2)") (class "Default")
      (node (ref "R305") (pin "1") (pinfunction "1_1") (pintype "passive"))
      (node (ref "U11") (pin "38") (pinfunction "INT_N/PME_N2_38") (pintype "output"))
    )
    (net (code "43") (name "Net-(U11A-ISET)") (class "Default")
      (node (ref "R299") (pin "1") (pinfunction "1_1") (pintype "passive"))
      (node (ref "U11") (pin "48") (pinfunction "ISET_48") (pintype "input"))
    )
    (net (code "44") (name "Net-(U11A-LED1{slash}PHYAD0{slash}PME_N1)") (class "Default")
      (node (ref "J11") (pin "13") (pinfunction "13_13") (pintype "passive"))
      (node (ref "R304") (pin "1") (pinfunction "1_1") (pintype "passive"))
      (node (ref "U11") (pin "17") (pinfunction "LED1/PHYAD0/PME_N1_17") (pintype "bidirectional"))
    )
    (net (code "45") (name "Net-(U11A-LED2{slash}PHYAD1)") (class "Default")
      (node (ref "J11") (pin "17") (pinfunction "17_17") (pintype "passive"))
      (node (ref "R307") (pin "1") (pinfunction "1_1") (pintype "passive"))
      (node (ref "U11") (pin "15") (pinfunction "LED2/PHYAD1_15") (pintype "bidirectional"))
    )
    (net (code "46") (name "Net-(U11A-RESET_N)") (class "Default")
      (node (ref "R301") (pin "1") (pinfunction "1_1") (pintype "passive"))
      (node (ref "U11") (pin "42") (pinfunction "RESET_N_42") (pintype "input"))
    )
    (net (code "47") (name "Net-(U11A-XI)") (class "Default")
      (node (ref "U11") (pin "46") (pinfunction "XI_46") (pintype "input"))
      (node (ref "U24") (pin "3") (pinfunction "OUTPUT_3") (pintype "passive"))
    )
    (net (code "48") (name "Net-(U24-TRI-STATE)") (class "Default")
      (node (ref "R311") (pin "2") (pinfunction "2_2") (pintype "passive"))
      (node (ref "U24") (pin "1") (pinfunction "TRI-STATE_1") (pintype "passive"))
    )
    (net (code "49") (name "Net-(U25-ADJ)") (class "Default")
      (node (ref "R314") (pin "1") (pinfunction "1_1") (pintype "passive"))
      (node (ref "R315") (pin "2") (pinfunction "2_2") (pintype "passive"))
      (node (ref "U25") (pin "8") (pinfunction "ADJ_8") (pintype "input"))
    )
    (net (code "50") (name "Net-(U25-~{SHDN})") (class "Default")
      (node (ref "R316") (pin "2") (pinfunction "2_2") (pintype "passive"))
      (node (ref "U25") (pin "6") (pinfunction "~{SHDN}_6") (pintype "input"))
    )
    (net (code "51") (name "unconnected-(J11-Pad15)") (class "Default")
      (node (ref "J11") (pin "15") (pinfunction "15_15") (pintype "passive"))
    )
    (net (code "52") (name "unconnected-(U11A-LDO_O-Pad43)") (class "Default")
      (node (ref "U11") (pin "43") (pinfunction "LDO_O_43") (pintype "output"))
    )
    (net (code "53") (name "unconnected-(U11A-XO-Pad45)") (class "Default")
      (node (ref "U11") (pin "45") (pinfunction "XO_45") (pintype "passive"))
    )
    (net (code "54") (name "unconnected-(U11B-NC-Pad13)") (class "Default")
      (node (ref "U11") (pin "13") (pinfunction "NC_13") (pintype "passive"))
    )
    (net (code "55") (name "unconnected-(U11B-NC-Pad47)") (class "Default")
      (node (ref "U11") (pin "47") (pinfunction "NC_47") (pintype "passive"))
    )
    (net (code "56") (name "unconnected-(U25-PG-Pad7)") (class "Default")
      (node (ref "U25") (pin "7") (pinfunction "PG_7") (pintype "tri_state"))
    )
  )
)
